# Analog3.net
KiCad netlist of a schematic drawn in Altium Designer
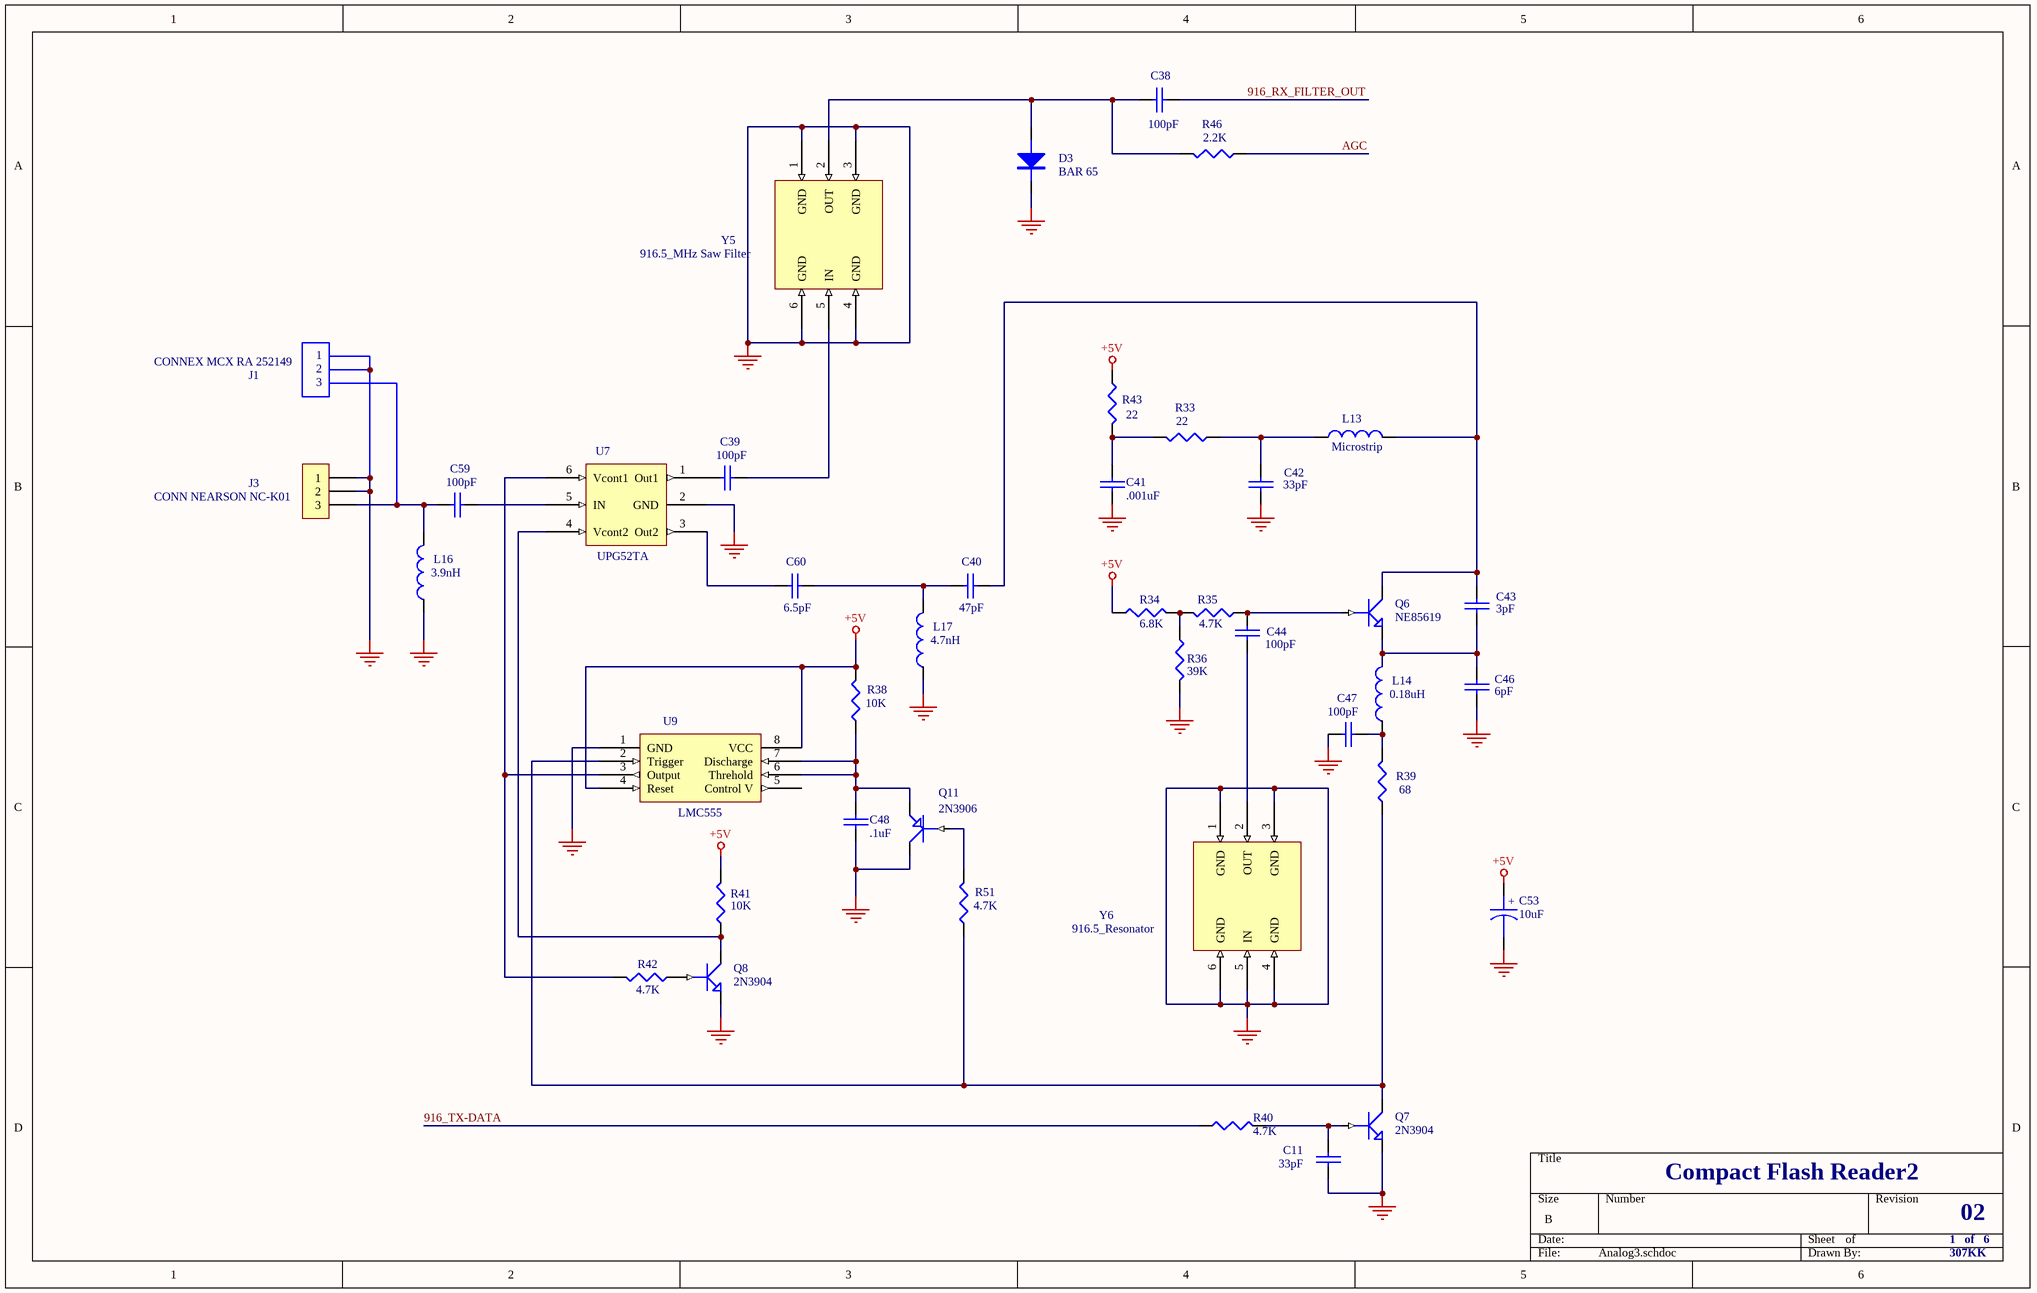
[diagram p0: Analog3.schdoc]

(export (version "E")
  (design (tool "Eeschema 10.0.6"))
  (components
    (comp (ref "C11")
      (value "33pF")
      (footprint "0603")
      (description "Capacitor")
      (libsource (lib "*") (part "CAP"))
    )
    (comp (ref "C38")
      (value "100pF")
      (footprint "0603")
      (description "Capacitor")
      (libsource (lib "*") (part "CAP"))
    )
    (comp (ref "C39")
      (value "100pF")
      (footprint "0603")
      (description "Capacitor")
      (libsource (lib "*") (part "CAP"))
    )
    (comp (ref "C40")
      (value "47pF")
      (footprint "0603")
      (description "Capacitor")
      (libsource (lib "*") (part "CAP"))
    )
    (comp (ref "C41")
      (value ".001uF")
      (footprint "0603")
      (description "Capacitor")
      (libsource (lib "*") (part "CAP"))
    )
    (comp (ref "C42")
      (value "33pF")
      (footprint "0603")
      (description "Capacitor")
      (libsource (lib "*") (part "CAP"))
    )
    (comp (ref "C43")
      (value "3pF")
      (footprint "0603")
      (description "Capacitor")
      (libsource (lib "*") (part "CAP"))
    )
    (comp (ref "C44")
      (value "100pF")
      (footprint "0603")
      (description "Capacitor")
      (libsource (lib "*") (part "CAP"))
    )
    (comp (ref "C46")
      (value "6pF")
      (footprint "0603")
      (description "Capacitor")
      (libsource (lib "*") (part "CAP"))
    )
    (comp (ref "C47")
      (value "100pF")
      (footprint "0603")
      (description "Capacitor")
      (libsource (lib "*") (part "CAP"))
    )
    (comp (ref "C48")
      (value ".1uF")
      (footprint "0603")
      (description "Capacitor")
      (libsource (lib "*") (part "CAP"))
    )
    (comp (ref "C53")
      (value "10uF")
      (footprint "CAP A CASE")
      (description "Capacitor")
      (libsource (lib "*") (part "CAPACITOR POL"))
    )
    (comp (ref "C59")
      (value "100pF")
      (footprint "0603")
      (description "Capacitor")
      (libsource (lib "*") (part "CAP"))
    )
    (comp (ref "C60")
      (value "6.5pF")
      (footprint "0603")
      (description "Capacitor")
      (libsource (lib "*") (part "CAP"))
    )
    (comp (ref "D3")
      (value "BAR 65")
      (footprint "DIODE SC79")
      (description "Diode")
      (libsource (lib "*") (part "DIODE"))
    )
    (comp (ref "J3")
      (value "CONN NEARSON NC-K01")
      (footprint "CONN NEARSON NC-K01")
      (description "Connector")
      (libsource (lib "*") (part "CON3"))
    )
    (comp (ref "L13") (value "Microstrip") (footprint "MICROSTRIP") (libsource (lib "*") (part "INDUCTOR")))
    (comp (ref "L14") (value "0.18uH") (footprint "0603") (libsource (lib "*") (part "INDUCTOR")))
    (comp (ref "L16") (value "3.9nH") (footprint "0603") (libsource (lib "*") (part "INDUCTOR")))
    (comp (ref "L17") (value "4.7nH") (footprint "0603") (libsource (lib "*") (part "INDUCTOR")))
    (comp (ref "Q6")
      (value "NE85619")
      (footprint "3 PIN ULTRA SUPER MINI MOLD")
      (description "NPN Transistor")
      (libsource (lib "*") (part "NPN1"))
    )
    (comp (ref "Q7")
      (value "2N3904")
      (footprint "SOT23 TRANS")
      (description "NPN Transistor")
      (libsource (lib "*") (part "NPN1"))
    )
    (comp (ref "Q8")
      (value "2N3904")
      (footprint "SOT23 TRANS")
      (description "NPN Transistor")
      (libsource (lib "*") (part "NPN1"))
    )
    (comp (ref "Q11")
      (value "2N3906")
      (footprint "SOT23 TRANS")
      (description "PNP Transistor")
      (libsource (lib "*") (part "PNP1"))
    )
    (comp (ref "R33") (value "22") (footprint "0603") (libsource (lib "*") (part "RESISTOR")))
    (comp (ref "R34") (value "6.8K") (footprint "0603") (libsource (lib "*") (part "RESISTOR")))
    (comp (ref "R35") (value "4.7K") (footprint "0603") (libsource (lib "*") (part "RESISTOR")))
    (comp (ref "R36") (value "39K") (footprint "0603") (libsource (lib "*") (part "RESISTOR")))
    (comp (ref "R38") (value "10K") (footprint "0603") (libsource (lib "*") (part "RESISTOR")))
    (comp (ref "R39") (value "68") (footprint "0603") (libsource (lib "*") (part "RESISTOR")))
    (comp (ref "R40") (value "4.7K") (footprint "0603") (libsource (lib "*") (part "RESISTOR")))
    (comp (ref "R41") (value "10K") (footprint "0603") (libsource (lib "*") (part "RESISTOR")))
    (comp (ref "R42") (value "4.7K") (footprint "0603") (libsource (lib "*") (part "RESISTOR")))
    (comp (ref "R43") (value "22") (footprint "0603") (libsource (lib "*") (part "RESISTOR")))
    (comp (ref "R46") (value "2.2K") (footprint "0603") (libsource (lib "*") (part "RESISTOR")))
    (comp (ref "R51") (value "4.7K") (footprint "0603") (libsource (lib "*") (part "RESISTOR")))
    (comp (ref "U7") (value "UPG52TA") (footprint "TO6") (libsource (lib "*") (part "UPG152TA_0")))
    (comp (ref "U9") (value "LMC555") (footprint "SO8 SMALL") (libsource (lib "*") (part "LMC555")))
    (comp (ref "Y5") (value "916.5_MHz Saw Filter") (libsource (lib "*") (part "RESONATOR3")))
    (comp (ref "Y6")
      (value "916.5_Resonator")
      (libsource (lib "Compact Flash Reader1_1") (part "RESONATOR3"))
    )
  )
  (nets
    (net (code "1") (name "+5V") (class "Default")
      (node (ref "C53") (pin "1") (pinfunction "1_1") (pintype "passive"))
      (node (ref "R34") (pin "1") (pinfunction "1_1") (pintype "passive"))
      (node (ref "R38") (pin "2") (pinfunction "2_2") (pintype "passive"))
      (node (ref "R41") (pin "2") (pinfunction "2_2") (pintype "passive"))
      (node (ref "R43") (pin "1") (pinfunction "1_1") (pintype "passive"))
      (node (ref "U9") (pin "4") (pinfunction "Reset_4") (pintype "input"))
      (node (ref "U9") (pin "8") (pinfunction "VCC_8") (pintype "power_in"))
    )
    (net (code "2") (name "/916_RX_FILTER_OUT") (class "Default")
      (node (ref "C38") (pin "2") (pinfunction "2_2") (pintype "passive"))
    )
    (net (code "3") (name "/916_TX-DATA") (class "Default")
      (node (ref "R40") (pin "1") (pinfunction "1_1") (pintype "passive"))
    )
    (net (code "4") (name "/AGC") (class "Default")
      (node (ref "R46") (pin "1") (pinfunction "1_1") (pintype "passive"))
    )
    (net (code "5") (name "GND_SIGNAL") (class "Default")
      (node (ref "C11") (pin "2") (pinfunction "2_2") (pintype "passive"))
      (node (ref "C41") (pin "2") (pinfunction "2_2") (pintype "passive"))
      (node (ref "C42") (pin "2") (pinfunction "2_2") (pintype "passive"))
      (node (ref "C46") (pin "2") (pinfunction "2_2") (pintype "passive"))
      (node (ref "C47") (pin "1") (pinfunction "1_1") (pintype "passive"))
      (node (ref "C48") (pin "2") (pinfunction "2_2") (pintype "passive"))
      (node (ref "C53") (pin "2") (pinfunction "2_2") (pintype "passive"))
      (node (ref "D3") (pin "K") (pinfunction "K_K") (pintype "passive"))
      (node (ref "J3") (pin "1") (pinfunction "1_1") (pintype "passive"))
      (node (ref "J3") (pin "2") (pinfunction "2_2") (pintype "passive"))
      (node (ref "L16") (pin "1") (pinfunction "1_1") (pintype "passive"))
      (node (ref "L17") (pin "1") (pinfunction "1_1") (pintype "passive"))
      (node (ref "Q11") (pin "C") (pinfunction "C_C") (pintype "passive"))
      (node (ref "Q7") (pin "E") (pinfunction "E_E") (pintype "passive"))
      (node (ref "Q8") (pin "E") (pinfunction "E_E") (pintype "passive"))
      (node (ref "R36") (pin "2") (pinfunction "2_2") (pintype "passive"))
      (node (ref "U7") (pin "2") (pinfunction "GND_2") (pintype "power_in"))
      (node (ref "U9") (pin "1") (pinfunction "GND_1") (pintype "power_in"))
      (node (ref "Y5") (pin "1") (pinfunction "GND_1") (pintype "input"))
      (node (ref "Y5") (pin "3") (pinfunction "GND_3") (pintype "input"))
      (node (ref "Y5") (pin "4") (pinfunction "GND_4") (pintype "input"))
      (node (ref "Y5") (pin "6") (pinfunction "GND_6") (pintype "input"))
      (node (ref "Y6") (pin "1") (pinfunction "GND_1") (pintype "input"))
      (node (ref "Y6") (pin "3") (pinfunction "GND_3") (pintype "input"))
      (node (ref "Y6") (pin "4") (pinfunction "GND_4") (pintype "input"))
      (node (ref "Y6") (pin "5") (pinfunction "IN_5") (pintype "input"))
      (node (ref "Y6") (pin "6") (pinfunction "GND_6") (pintype "input"))
    )
    (net (code "6") (name "Net-(C11-Pad1)") (class "Default")
      (node (ref "C11") (pin "1") (pinfunction "1_1") (pintype "passive"))
      (node (ref "Q7") (pin "B") (pinfunction "B_B") (pintype "input"))
      (node (ref "R40") (pin "2") (pinfunction "2_2") (pintype "passive"))
    )
    (net (code "7") (name "Net-(C40-Pad1)") (class "Default")
      (node (ref "C40") (pin "1") (pinfunction "1_1") (pintype "passive"))
      (node (ref "C60") (pin "2") (pinfunction "2_2") (pintype "passive"))
      (node (ref "L17") (pin "2") (pinfunction "2_2") (pintype "passive"))
    )
    (net (code "8") (name "Net-(C40-Pad2)") (class "Default")
      (node (ref "C40") (pin "2") (pinfunction "2_2") (pintype "passive"))
      (node (ref "C43") (pin "1") (pinfunction "1_1") (pintype "passive"))
      (node (ref "L13") (pin "2") (pinfunction "2_2") (pintype "passive"))
      (node (ref "Q6") (pin "C") (pinfunction "C_C") (pintype "passive"))
    )
    (net (code "9") (name "Net-(C41-Pad1)") (class "Default")
      (node (ref "C41") (pin "1") (pinfunction "1_1") (pintype "passive"))
      (node (ref "R33") (pin "2") (pinfunction "2_2") (pintype "passive"))
      (node (ref "R43") (pin "2") (pinfunction "2_2") (pintype "passive"))
    )
    (net (code "10") (name "Net-(C42-Pad1)") (class "Default")
      (node (ref "C42") (pin "1") (pinfunction "1_1") (pintype "passive"))
      (node (ref "L13") (pin "1") (pinfunction "1_1") (pintype "passive"))
      (node (ref "R33") (pin "1") (pinfunction "1_1") (pintype "passive"))
    )
    (net (code "11") (name "Net-(C43-Pad2)") (class "Default")
      (node (ref "C43") (pin "2") (pinfunction "2_2") (pintype "passive"))
      (node (ref "C46") (pin "1") (pinfunction "1_1") (pintype "passive"))
      (node (ref "L14") (pin "2") (pinfunction "2_2") (pintype "passive"))
      (node (ref "Q6") (pin "E") (pinfunction "E_E") (pintype "passive"))
    )
    (net (code "12") (name "Net-(C44-Pad1)") (class "Default")
      (node (ref "C44") (pin "1") (pinfunction "1_1") (pintype "passive"))
      (node (ref "Q6") (pin "B") (pinfunction "B_B") (pintype "input"))
      (node (ref "R35") (pin "1") (pinfunction "1_1") (pintype "passive"))
    )
    (net (code "13") (name "Net-(C47-Pad2)") (class "Default")
      (node (ref "C47") (pin "2") (pinfunction "2_2") (pintype "passive"))
      (node (ref "L14") (pin "1") (pinfunction "1_1") (pintype "passive"))
      (node (ref "R39") (pin "2") (pinfunction "2_2") (pintype "passive"))
    )
    (net (code "14") (name "Net-(C59-Pad1)") (class "Default")
      (node (ref "C59") (pin "1") (pinfunction "1_1") (pintype "passive"))
      (node (ref "J3") (pin "3") (pinfunction "3_3") (pintype "passive"))
      (node (ref "L16") (pin "2") (pinfunction "2_2") (pintype "passive"))
    )
    (net (code "15") (name "Net-(Q8-PadB)") (class "Default")
      (node (ref "Q8") (pin "B") (pinfunction "B_B") (pintype "input"))
      (node (ref "R42") (pin "1") (pinfunction "1_1") (pintype "passive"))
    )
    (net (code "16") (name "Net-(Q11-PadB)") (class "Default")
      (node (ref "Q11") (pin "B") (pinfunction "B_B") (pintype "input"))
      (node (ref "R51") (pin "2") (pinfunction "2_2") (pintype "passive"))
    )
    (net (code "17") (name "Net-(R34-Pad2)") (class "Default")
      (node (ref "R34") (pin "2") (pinfunction "2_2") (pintype "passive"))
      (node (ref "R35") (pin "2") (pinfunction "2_2") (pintype "passive"))
      (node (ref "R36") (pin "1") (pinfunction "1_1") (pintype "passive"))
    )
    (net (code "18") (name "Net-(U7-IN)") (class "Default")
      (node (ref "C59") (pin "2") (pinfunction "2_2") (pintype "passive"))
      (node (ref "U7") (pin "5") (pinfunction "IN_5") (pintype "input"))
    )
    (net (code "19") (name "Net-(U7-Out1)") (class "Default")
      (node (ref "C39") (pin "1") (pinfunction "1_1") (pintype "passive"))
      (node (ref "U7") (pin "1") (pinfunction "Out1_1") (pintype "output"))
    )
    (net (code "20") (name "Net-(U7-Out2)") (class "Default")
      (node (ref "C60") (pin "1") (pinfunction "1_1") (pintype "passive"))
      (node (ref "U7") (pin "3") (pinfunction "Out2_3") (pintype "output"))
    )
    (net (code "21") (name "Net-(U7-Vcont1)") (class "Default")
      (node (ref "R42") (pin "2") (pinfunction "2_2") (pintype "passive"))
      (node (ref "U7") (pin "6") (pinfunction "Vcont1_6") (pintype "input"))
      (node (ref "U9") (pin "3") (pinfunction "Output_3") (pintype "output"))
    )
    (net (code "22") (name "Net-(U7-Vcont2)") (class "Default")
      (node (ref "Q8") (pin "C") (pinfunction "C_C") (pintype "passive"))
      (node (ref "R41") (pin "1") (pinfunction "1_1") (pintype "passive"))
      (node (ref "U7") (pin "4") (pinfunction "Vcont2_4") (pintype "input"))
    )
    (net (code "23") (name "Net-(U9-Discharge)") (class "Default")
      (node (ref "C48") (pin "1") (pinfunction "1_1") (pintype "passive"))
      (node (ref "Q11") (pin "E") (pinfunction "E_E") (pintype "passive"))
      (node (ref "R38") (pin "1") (pinfunction "1_1") (pintype "passive"))
      (node (ref "U9") (pin "6") (pinfunction "Threhold_6") (pintype "input"))
      (node (ref "U9") (pin "7") (pinfunction "Discharge_7") (pintype "input"))
    )
    (net (code "24") (name "Net-(U9-Trigger)") (class "Default")
      (node (ref "Q7") (pin "C") (pinfunction "C_C") (pintype "passive"))
      (node (ref "R39") (pin "1") (pinfunction "1_1") (pintype "passive"))
      (node (ref "R51") (pin "1") (pinfunction "1_1") (pintype "passive"))
      (node (ref "U9") (pin "2") (pinfunction "Trigger_2") (pintype "input"))
    )
    (net (code "25") (name "Net-(Y5-IN)") (class "Default")
      (node (ref "C39") (pin "2") (pinfunction "2_2") (pintype "passive"))
      (node (ref "Y5") (pin "5") (pinfunction "IN_5") (pintype "input"))
    )
    (net (code "26") (name "Net-(Y5-OUT)") (class "Default")
      (node (ref "C38") (pin "1") (pinfunction "1_1") (pintype "passive"))
      (node (ref "D3") (pin "A") (pinfunction "A_A") (pintype "passive"))
      (node (ref "R46") (pin "2") (pinfunction "2_2") (pintype "passive"))
      (node (ref "Y5") (pin "2") (pinfunction "OUT_2") (pintype "input"))
    )
    (net (code "27") (name "Net-(Y6-OUT)") (class "Default")
      (node (ref "C44") (pin "2") (pinfunction "2_2") (pintype "passive"))
      (node (ref "Y6") (pin "2") (pinfunction "OUT_2") (pintype "input"))
    )
    (net (code "28") (name "unconnected-(U9-Control_V-Pad5)") (class "Default")
      (node (ref "U9") (pin "5") (pinfunction "Control_V_5") (pintype "output"))
    )
  )
)
